# CAM_CONNECTOR.net
KiCad netlist of a schematic drawn in Altium Designer
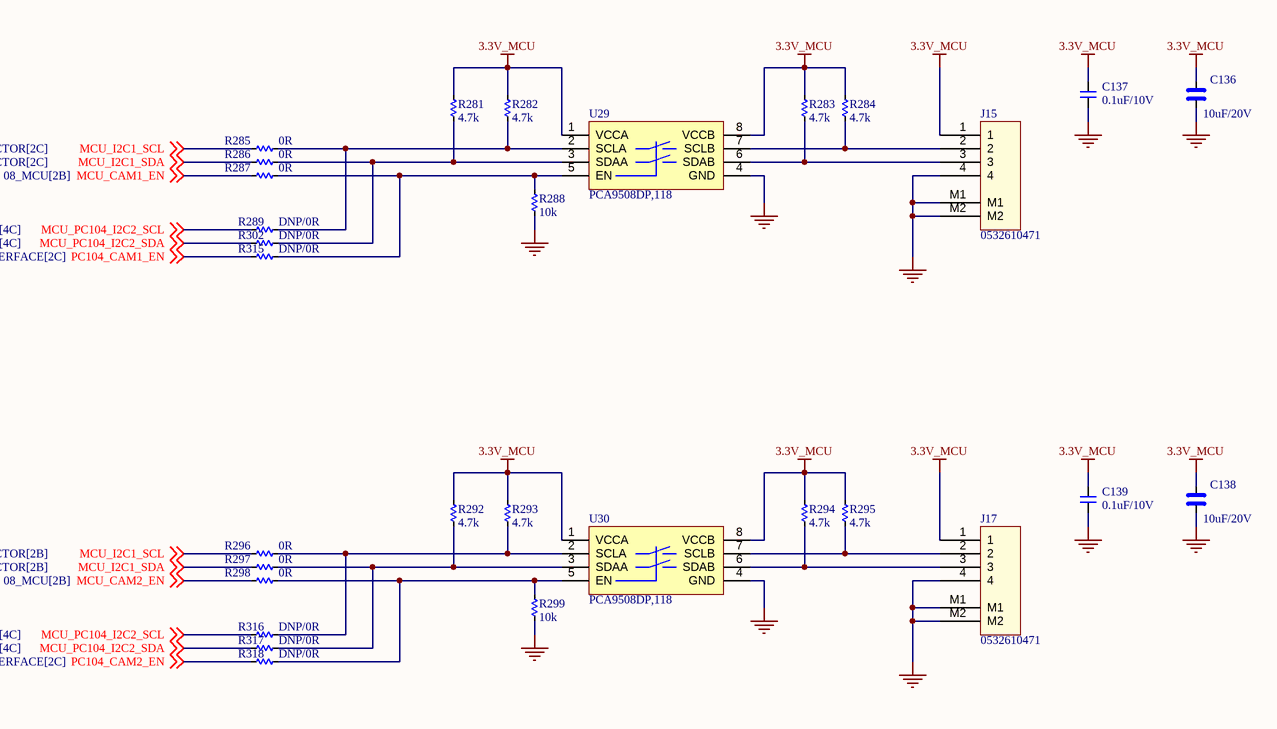
[diagram p0: CAM_CONNECTOR.SchDoc]

(export (version "E")
  (design (tool "Eeschema 10.0.6"))
  (components
    (comp (ref "C136")
      (value "10uF/20V")
      (footprint "CAP_C_2012X110")
      (description "CAP High Value")
      (libsource (lib "LABLIB") (part "_CAP_C_High_2"))
    )
    (comp (ref "C137")
      (value "0.1uF/10V")
      (footprint "CAP_C_1005X50_L")
      (description "CAP")
      (libsource (lib "LABLIB") (part "_CAP_C_2"))
    )
    (comp (ref "C138")
      (value "10uF/20V")
      (footprint "CAP_C_2012X110")
      (description "CAP High Value")
      (libsource (lib "LABLIB") (part "_CAP_C_High_2"))
    )
    (comp (ref "C139")
      (value "0.1uF/10V")
      (footprint "CAP_C_1005X50_L")
      (description "CAP")
      (libsource (lib "LABLIB") (part "_CAP_C_2"))
    )
    (comp (ref "J15")
      (value "0532610471")
      (footprint "MOLEX_0532610471")
      (libsource (lib "BEE-DAL_EXP_sche") (part "Header 4x1_2M_1"))
    )
    (comp (ref "J17")
      (value "0532610471")
      (footprint "MOLEX_0532610471")
      (libsource (lib "BEE-DAL_EXP_sche") (part "Header 4x1_2M_1"))
    )
    (comp (ref "R281")
      (value "4.7k")
      (footprint "RES_C_1005x30_L")
      (description "RES")
      (libsource (lib "LABLIB") (part "_RES_B_2"))
    )
    (comp (ref "R282")
      (value "4.7k")
      (footprint "RES_C_1005x30_L")
      (description "RES")
      (libsource (lib "LABLIB") (part "_RES_B_2"))
    )
    (comp (ref "R283")
      (value "4.7k")
      (footprint "RES_C_1005x30_L")
      (description "RES")
      (libsource (lib "LABLIB") (part "_RES_B_2"))
    )
    (comp (ref "R284")
      (value "4.7k")
      (footprint "RES_C_1005x30_L")
      (description "RES")
      (libsource (lib "LABLIB") (part "_RES_B_2"))
    )
    (comp (ref "R285")
      (value "0R")
      (footprint "RES_C_1005x30_L")
      (description "RES")
      (libsource (lib "LABLIB") (part "_RES_B_2"))
    )
    (comp (ref "R286")
      (value "0R")
      (footprint "RES_C_1005x30_L")
      (description "RES")
      (libsource (lib "LABLIB") (part "_RES_B_2"))
    )
    (comp (ref "R287")
      (value "0R")
      (footprint "RES_C_1005x30_L")
      (description "RES")
      (libsource (lib "LABLIB") (part "_RES_B_2"))
    )
    (comp (ref "R288")
      (value "10k")
      (footprint "RES_C_1005X40")
      (description "RES")
      (libsource (lib "LABLIB") (part "_RES_B_2"))
    )
    (comp (ref "R289")
      (value "DNP/0R")
      (footprint "RES_C_1005X40")
      (description "RES")
      (libsource (lib "LABLIB") (part "_RES_B_2"))
    )
    (comp (ref "R292")
      (value "4.7k")
      (footprint "RES_C_1005x30_L")
      (description "RES")
      (libsource (lib "LABLIB") (part "_RES_B_2"))
    )
    (comp (ref "R293")
      (value "4.7k")
      (footprint "RES_C_1005x30_L")
      (description "RES")
      (libsource (lib "LABLIB") (part "_RES_B_2"))
    )
    (comp (ref "R294")
      (value "4.7k")
      (footprint "RES_C_1005x30_L")
      (description "RES")
      (libsource (lib "LABLIB") (part "_RES_B_2"))
    )
    (comp (ref "R295")
      (value "4.7k")
      (footprint "RES_C_1005x30_L")
      (description "RES")
      (libsource (lib "LABLIB") (part "_RES_B_2"))
    )
    (comp (ref "R296")
      (value "0R")
      (footprint "RES_C_1005x30_L")
      (description "RES")
      (libsource (lib "LABLIB") (part "_RES_B_2"))
    )
    (comp (ref "R297")
      (value "0R")
      (footprint "RES_C_1005x30_L")
      (description "RES")
      (libsource (lib "LABLIB") (part "_RES_B_2"))
    )
    (comp (ref "R298")
      (value "0R")
      (footprint "RES_C_1005x30_L")
      (description "RES")
      (libsource (lib "LABLIB") (part "_RES_B_2"))
    )
    (comp (ref "R299")
      (value "10k")
      (footprint "RES_C_1005X40")
      (description "RES")
      (libsource (lib "LABLIB") (part "_RES_B_2"))
    )
    (comp (ref "R302")
      (value "DNP/0R")
      (footprint "RES_C_1005X40")
      (description "RES")
      (libsource (lib "LABLIB") (part "_RES_B_2"))
    )
    (comp (ref "R315")
      (value "DNP/0R")
      (footprint "RES_C_1005X40")
      (description "RES")
      (libsource (lib "LABLIB") (part "_RES_B_2"))
    )
    (comp (ref "R316")
      (value "DNP/0R")
      (footprint "RES_C_1005X40")
      (description "RES")
      (libsource (lib "LABLIB") (part "_RES_B_2"))
    )
    (comp (ref "R317")
      (value "DNP/0R")
      (footprint "RES_C_1005X40")
      (description "RES")
      (libsource (lib "LABLIB") (part "_RES_B_2"))
    )
    (comp (ref "R318")
      (value "DNP/0R")
      (footprint "RES_C_1005X40")
      (description "RES")
      (libsource (lib "LABLIB") (part "_RES_B_2"))
    )
    (comp (ref "U29")
      (value "PCA9508DP,118")
      (footprint "TSOP8")
      (libsource (lib "BEE-DAL_EXP_sche") (part "PCA9508DP,118"))
    )
    (comp (ref "U30")
      (value "PCA9508DP,118")
      (footprint "TSOP8")
      (libsource (lib "BEE-DAL_EXP_sche") (part "PCA9508DP,118"))
    )
  )
  (nets
    (net (code "1") (name "3.3V_MCU") (class "Default")
      (node (ref "C136") (pin "1") (pinfunction "1_1") (pintype "passive"))
      (node (ref "C137") (pin "2") (pinfunction "2_2") (pintype "passive"))
      (node (ref "C138") (pin "1") (pinfunction "1_1") (pintype "passive"))
      (node (ref "C139") (pin "2") (pinfunction "2_2") (pintype "passive"))
      (node (ref "J15") (pin "1") (pinfunction "1_1") (pintype "passive"))
      (node (ref "J17") (pin "1") (pinfunction "1_1") (pintype "passive"))
      (node (ref "R281") (pin "1") (pinfunction "1_1") (pintype "passive"))
      (node (ref "R282") (pin "1") (pinfunction "1_1") (pintype "passive"))
      (node (ref "R283") (pin "1") (pinfunction "1_1") (pintype "passive"))
      (node (ref "R284") (pin "1") (pinfunction "1_1") (pintype "passive"))
      (node (ref "R292") (pin "1") (pinfunction "1_1") (pintype "passive"))
      (node (ref "R293") (pin "1") (pinfunction "1_1") (pintype "passive"))
      (node (ref "R294") (pin "1") (pinfunction "1_1") (pintype "passive"))
      (node (ref "R295") (pin "1") (pinfunction "1_1") (pintype "passive"))
      (node (ref "U29") (pin "1") (pinfunction "VCCA_1") (pintype "passive"))
      (node (ref "U29") (pin "8") (pinfunction "VCCB_8") (pintype "passive"))
      (node (ref "U30") (pin "1") (pinfunction "VCCA_1") (pintype "passive"))
      (node (ref "U30") (pin "8") (pinfunction "VCCB_8") (pintype "passive"))
    )
    (net (code "2") (name "GND") (class "Default")
      (node (ref "C136") (pin "2") (pinfunction "2_2") (pintype "passive"))
      (node (ref "C137") (pin "1") (pinfunction "1_1") (pintype "passive"))
      (node (ref "C138") (pin "2") (pinfunction "2_2") (pintype "passive"))
      (node (ref "C139") (pin "1") (pinfunction "1_1") (pintype "passive"))
      (node (ref "J15") (pin "4") (pinfunction "4_4") (pintype "passive"))
      (node (ref "J15") (pin "M1") (pinfunction "M1_M1") (pintype "passive"))
      (node (ref "J15") (pin "M2") (pinfunction "M2_M2") (pintype "passive"))
      (node (ref "J17") (pin "4") (pinfunction "4_4") (pintype "passive"))
      (node (ref "J17") (pin "M1") (pinfunction "M1_M1") (pintype "passive"))
      (node (ref "J17") (pin "M2") (pinfunction "M2_M2") (pintype "passive"))
      (node (ref "R288") (pin "2") (pinfunction "2_2") (pintype "passive"))
      (node (ref "R299") (pin "2") (pinfunction "2_2") (pintype "passive"))
      (node (ref "U29") (pin "4") (pinfunction "GND_4") (pintype "passive"))
      (node (ref "U30") (pin "4") (pinfunction "GND_4") (pintype "passive"))
    )
    (net (code "3") (name "MCU_CAM1_EN") (class "Default")
      (node (ref "R287") (pin "1") (pinfunction "1_1") (pintype "passive"))
    )
    (net (code "4") (name "MCU_CAM2_EN") (class "Default")
      (node (ref "R298") (pin "1") (pinfunction "1_1") (pintype "passive"))
    )
    (net (code "5") (name "MCU_I2C1_SCL") (class "Default")
      (node (ref "R285") (pin "1") (pinfunction "1_1") (pintype "passive"))
      (node (ref "R296") (pin "1") (pinfunction "1_1") (pintype "passive"))
    )
    (net (code "6") (name "MCU_I2C1_SDA") (class "Default")
      (node (ref "R286") (pin "1") (pinfunction "1_1") (pintype "passive"))
      (node (ref "R297") (pin "1") (pinfunction "1_1") (pintype "passive"))
    )
    (net (code "7") (name "MCU_PC104_I2C2_SCL") (class "Default")
      (node (ref "R289") (pin "1") (pinfunction "1_1") (pintype "passive"))
      (node (ref "R316") (pin "1") (pinfunction "1_1") (pintype "passive"))
    )
    (net (code "8") (name "MCU_PC104_I2C2_SDA") (class "Default")
      (node (ref "R302") (pin "1") (pinfunction "1_1") (pintype "passive"))
      (node (ref "R317") (pin "1") (pinfunction "1_1") (pintype "passive"))
    )
    (net (code "9") (name "Net-(U29-EN)") (class "Default")
      (node (ref "R287") (pin "2") (pinfunction "2_2") (pintype "passive"))
      (node (ref "R288") (pin "1") (pinfunction "1_1") (pintype "passive"))
      (node (ref "R315") (pin "2") (pinfunction "2_2") (pintype "passive"))
      (node (ref "U29") (pin "5") (pinfunction "EN_5") (pintype "passive"))
    )
    (net (code "10") (name "Net-(U29-SCLA)") (class "Default")
      (node (ref "R282") (pin "2") (pinfunction "2_2") (pintype "passive"))
      (node (ref "R285") (pin "2") (pinfunction "2_2") (pintype "passive"))
      (node (ref "R289") (pin "2") (pinfunction "2_2") (pintype "passive"))
      (node (ref "U29") (pin "2") (pinfunction "SCLA_2") (pintype "passive"))
    )
    (net (code "11") (name "Net-(U29-SCLB)") (class "Default")
      (node (ref "J15") (pin "2") (pinfunction "2_2") (pintype "passive"))
      (node (ref "R284") (pin "2") (pinfunction "2_2") (pintype "passive"))
      (node (ref "U29") (pin "7") (pinfunction "SCLB_7") (pintype "passive"))
    )
    (net (code "12") (name "Net-(U29-SDAA)") (class "Default")
      (node (ref "R281") (pin "2") (pinfunction "2_2") (pintype "passive"))
      (node (ref "R286") (pin "2") (pinfunction "2_2") (pintype "passive"))
      (node (ref "R302") (pin "2") (pinfunction "2_2") (pintype "passive"))
      (node (ref "U29") (pin "3") (pinfunction "SDAA_3") (pintype "passive"))
    )
    (net (code "13") (name "Net-(U29-SDAB)") (class "Default")
      (node (ref "J15") (pin "3") (pinfunction "3_3") (pintype "passive"))
      (node (ref "R283") (pin "2") (pinfunction "2_2") (pintype "passive"))
      (node (ref "U29") (pin "6") (pinfunction "SDAB_6") (pintype "passive"))
    )
    (net (code "14") (name "Net-(U30-EN)") (class "Default")
      (node (ref "R298") (pin "2") (pinfunction "2_2") (pintype "passive"))
      (node (ref "R299") (pin "1") (pinfunction "1_1") (pintype "passive"))
      (node (ref "R318") (pin "2") (pinfunction "2_2") (pintype "passive"))
      (node (ref "U30") (pin "5") (pinfunction "EN_5") (pintype "passive"))
    )
    (net (code "15") (name "Net-(U30-SCLA)") (class "Default")
      (node (ref "R293") (pin "2") (pinfunction "2_2") (pintype "passive"))
      (node (ref "R296") (pin "2") (pinfunction "2_2") (pintype "passive"))
      (node (ref "R316") (pin "2") (pinfunction "2_2") (pintype "passive"))
      (node (ref "U30") (pin "2") (pinfunction "SCLA_2") (pintype "passive"))
    )
    (net (code "16") (name "Net-(U30-SCLB)") (class "Default")
      (node (ref "J17") (pin "2") (pinfunction "2_2") (pintype "passive"))
      (node (ref "R295") (pin "2") (pinfunction "2_2") (pintype "passive"))
      (node (ref "U30") (pin "7") (pinfunction "SCLB_7") (pintype "passive"))
    )
    (net (code "17") (name "Net-(U30-SDAA)") (class "Default")
      (node (ref "R292") (pin "2") (pinfunction "2_2") (pintype "passive"))
      (node (ref "R297") (pin "2") (pinfunction "2_2") (pintype "passive"))
      (node (ref "R317") (pin "2") (pinfunction "2_2") (pintype "passive"))
      (node (ref "U30") (pin "3") (pinfunction "SDAA_3") (pintype "passive"))
    )
    (net (code "18") (name "Net-(U30-SDAB)") (class "Default")
      (node (ref "J17") (pin "3") (pinfunction "3_3") (pintype "passive"))
      (node (ref "R294") (pin "2") (pinfunction "2_2") (pintype "passive"))
      (node (ref "U30") (pin "6") (pinfunction "SDAB_6") (pintype "passive"))
    )
    (net (code "19") (name "PC104_CAM1_EN") (class "Default")
      (node (ref "R315") (pin "1") (pinfunction "1_1") (pintype "passive"))
    )
    (net (code "20") (name "PC104_CAM2_EN") (class "Default")
      (node (ref "R318") (pin "1") (pinfunction "1_1") (pintype "passive"))
    )
  )
)
